# Main.net
KiCad netlist of a schematic drawn in Altium Designer
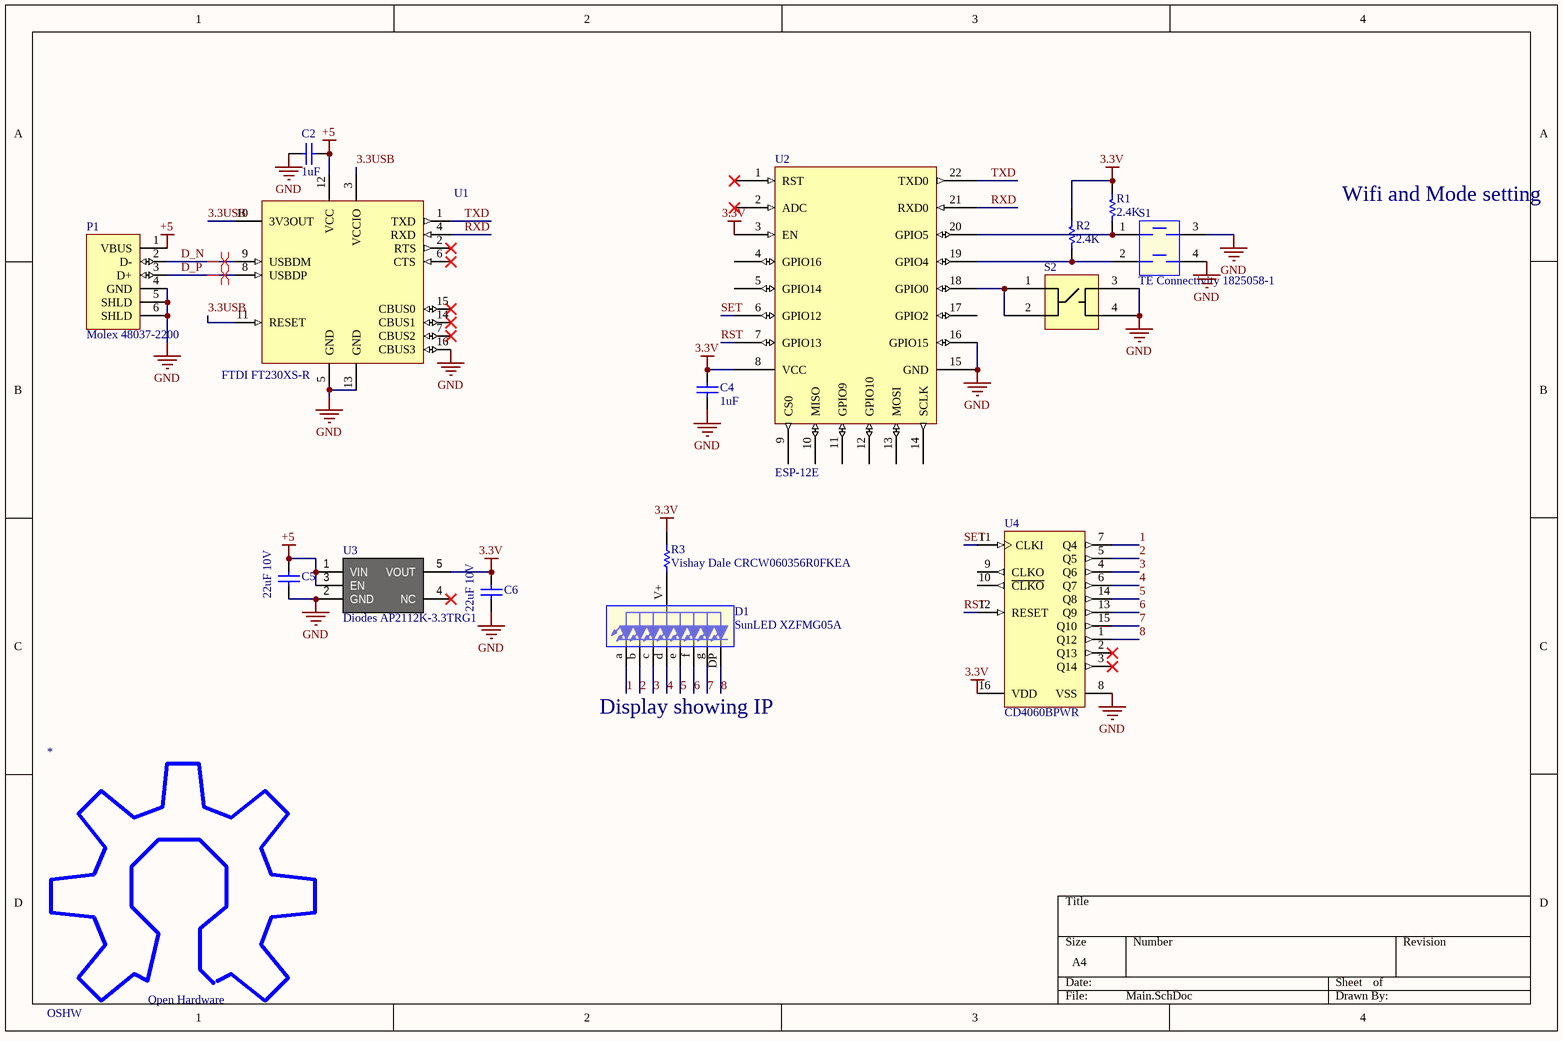
[diagram p0: Main.SchDoc]

(export (version "E")
  (design (tool "Eeschema 10.0.6"))
  (components
    (comp (ref "*")
      (value "OSHW")
      (footprint "PCB-wvhvgo6g2u4p9maf3omu-1")
      (libsource (lib "FavoritesLibrary") (part "SYM-yq9j37g916g0fiiuunoj-1"))
    )
    (comp (ref "C2")
      (value "1uF")
      (footprint "CAPC1608X90X35ML15T15")
      (description "CAP CER 1UF 16V 10% X5R 0603")
      (libsource (lib "CommunityVault") (part "CMP-126011-2"))
    )
    (comp (ref "C4")
      (value "1uF")
      (footprint "CAPC1608X90X35ML15T15")
      (description "CAP CER 1UF 16V 10% X5R 0603")
      (libsource (lib "CommunityVault") (part "CMP-126011-2"))
    )
    (comp (ref "C5")
      (value "22uF 10V")
      (footprint "CAPC3216X88X50NL20T25")
      (description "CAP CER 22UF 10V Y5V 1206")
      (fields
        (field (name "TOLERANCE") "-20%, +80%")
        (field (name "MANUFACTURER PART NUMBER") "LMK316F226ZL-T")
      )
      (libsource (lib "CommunityVault") (part "CMP-120806-1"))
    )
    (comp (ref "C6")
      (value "22uF 10V")
      (footprint "CAPC3216X88X50NL20T25")
      (description "CAP CER 22UF 10V Y5V 1206")
      (fields
        (field (name "TOLERANCE") "-20%, +80%")
        (field (name "MANUFACTURER PART NUMBER") "LMK316F226ZL-T")
      )
      (libsource (lib "CommunityVault") (part "CMP-120806-1"))
    )
    (comp (ref "D1")
      (value "SunLED XZFMG05A")
      (footprint "PCB-oie4hyh8z6kz1fe8odf0-1")
      (description "Display Led 0.2\" Green Ca Smd")
      (fields (field (name "MANUFACTURER PART NUMBER") "XZFMG05A"))
      (libsource (lib "CommunityVault") (part "SYM-790ab255a53aa6cd-1"))
    )
    (comp (ref "P1")
      (value "Molex 48037-2200")
      (footprint "PCB-2v2vzbs0gio7atqgwime-1")
      (description "Conn.; Data; USB; Plug; Shielded; Type A; Rt. Angle; SMT; Gold Plating")
      (fields (field (name "MANUFACTURER PART NUMBER") "48037-2200"))
      (libsource (lib "FavoritesLibrary") (part "SYM-d9a510daebca0662-1"))
    )
    (comp (ref "R1")
      (value "2.4K")
      (footprint "RESC1608X55X25ML10T15")
      (description "Res Thick Film 0603 2.4K Ohm 5% 1/10W 100ppm/C Molded SMD SMD Paper T/R")
      (fields
        (field (name "MANUFACTURER") "Philips (Mepco)")
        (field (name "MANUFACTURER PART NUMBER") "RC0603JR-072K4L")
      )
      (libsource (lib "CommunityVault") (part "CMP-13559605-1"))
    )
    (comp (ref "R2")
      (value "2.4K")
      (footprint "RESC1608X55X25ML10T15")
      (description "Res Thick Film 0603 2.4K Ohm 5% 1/10W 100ppm/C Molded SMD SMD Paper T/R")
      (fields
        (field (name "MANUFACTURER") "Philips (Mepco)")
        (field (name "MANUFACTURER PART NUMBER") "RC0603JR-072K4L")
      )
      (libsource (lib "CommunityVault") (part "CMP-13559605-1"))
    )
    (comp (ref "R3")
      (value "Vishay Dale CRCW060356R0FKEA")
      (footprint "RESC1609X50X30LL10T20")
      (description "RES SMD 56 OHM 1% 1/10W 0603")
      (libsource (lib "CommunityVault") (part "RES-2"))
    )
    (comp (ref "S1")
      (value "TE Connectivity 1825058-1")
      (footprint "PCB-oate9ly85fgayrvi93ce-1")
      (description "Switch DIP OFF ON SPST 2 Raised Slide 0.1A 24VDC Gull Wing 2.54mm SMD Tube")
      (fields (field (name "MANUFACTURER PART NUMBER") "1825058-1"))
      (libsource (lib "FavoritesLibrary") (part "SYM-446e8fa1c71e9ba9-1"))
    )
    (comp (ref "S2")
      (value "TE Connectivity (Tyco Electronics) / ALCOSWITCH FSM4JSMATR")
      (footprint "PCB-1274972-1")
      (description "SWITCH TACTILE SPST-NO 0.05A 24V")
      (libsource (lib "CommunityVault") (part "CMP-1274972-2"))
    )
    (comp (ref "U1")
      (value "FTDI FT230XS-R")
      (footprint "SSOP16-0.635-5X4MM")
      (description "Interface; USB-basic UART; Number of pins CBUS: 4; tape; SSOP16")
      (fields (field (name "MANUFACTURER PART NUMBER") "FT230XS-R"))
      (libsource (lib "CommunityVault") (part "FTDI-FT230XS-R-16"))
    )
    (comp (ref "U2")
      (value "ESP-12E")
      (footprint "PCB-20357682-7")
      (description "ESP8266 WiFi Module - ESP-12E")
      (libsource (lib "CommunityVault") (part "SYM-20357682-8"))
    )
    (comp (ref "U3")
      (value "Diodes AP2112K-3.3TRG1")
      (footprint "PCB-15095236-1")
      (description "IC REG LDO 3.3V 0.6A SOT25")
      (libsource (lib "CommunityVault") (part "SYM-15095236-1"))
    )
    (comp (ref "U4")
      (value "CD4060BPWR")
      (footprint "TI-PW16_N")
      (libsource (lib "CommunityVault") (part "TI-CD4060B-16"))
    )
  )
  (nets
    (net (code "1") (name "+5") (class "Default")
      (node (ref "C2") (pin "2") (pinfunction "2_2") (pintype "passive"))
      (node (ref "C5") (pin "2") (pinfunction "2_2") (pintype "passive"))
      (node (ref "P1") (pin "1") (pinfunction "VBUS_1") (pintype "power_in"))
      (node (ref "U1") (pin "12") (pinfunction "VCC_12") (pintype "power_in"))
      (node (ref "U3") (pin "1") (pinfunction "VIN_1") (pintype "passive"))
      (node (ref "U3") (pin "3") (pinfunction "EN_3") (pintype "passive"))
    )
    (net (code "2") (name "/1") (class "Default")
      (node (ref "D1") (pin "a") (pintype "passive"))
      (node (ref "U4") (pin "7") (pinfunction "Q4_7") (pintype "output"))
    )
    (net (code "3") (name "/2") (class "Default")
      (node (ref "D1") (pin "b") (pintype "passive"))
      (node (ref "U4") (pin "5") (pinfunction "Q5_5") (pintype "output"))
    )
    (net (code "4") (name "/3") (class "Default")
      (node (ref "D1") (pin "c") (pintype "passive"))
      (node (ref "U4") (pin "4") (pinfunction "Q6_4") (pintype "output"))
    )
    (net (code "5") (name "/3.3USB") (class "Default")
      (node (ref "U1") (pin "10") (pinfunction "3V3OUT_10") (pintype "power_in"))
      (node (ref "U1") (pin "11") (pinfunction "RESET_11") (pintype "input"))
      (node (ref "U1") (pin "3") (pinfunction "VCCIO_3") (pintype "power_in"))
    )
    (net (code "6") (name "/4") (class "Default")
      (node (ref "D1") (pin "d") (pintype "passive"))
      (node (ref "U4") (pin "6") (pinfunction "Q7_6") (pintype "output"))
    )
    (net (code "7") (name "/5") (class "Default")
      (node (ref "D1") (pin "e") (pintype "passive"))
      (node (ref "U4") (pin "14") (pinfunction "Q8_14") (pintype "output"))
    )
    (net (code "8") (name "/6") (class "Default")
      (node (ref "D1") (pin "f") (pintype "passive"))
      (node (ref "U4") (pin "13") (pinfunction "Q9_13") (pintype "output"))
    )
    (net (code "9") (name "/7") (class "Default")
      (node (ref "D1") (pin "g") (pintype "passive"))
      (node (ref "U4") (pin "15") (pinfunction "Q10_15") (pintype "output"))
    )
    (net (code "10") (name "/8") (class "Default")
      (node (ref "D1") (pin "DP") (pintype "passive"))
      (node (ref "U4") (pin "1") (pinfunction "Q12_1") (pintype "output"))
    )
    (net (code "11") (name "/D_N") (class "Default")
      (node (ref "P1") (pin "2") (pinfunction "D-_2") (pintype "bidirectional"))
      (node (ref "U1") (pin "9") (pinfunction "USBDM_9") (pintype "input"))
    )
    (net (code "12") (name "/D_P") (class "Default")
      (node (ref "P1") (pin "3") (pinfunction "D+_3") (pintype "bidirectional"))
      (node (ref "U1") (pin "8") (pinfunction "USBDP_8") (pintype "input"))
    )
    (net (code "13") (name "/RST") (class "Default")
      (node (ref "U2") (pin "7") (pinfunction "GPIO13_7") (pintype "bidirectional"))
      (node (ref "U4") (pin "12") (pinfunction "RESET_12") (pintype "input"))
    )
    (net (code "14") (name "/RXD") (class "Default")
      (node (ref "U1") (pin "4") (pinfunction "RXD_4") (pintype "input"))
      (node (ref "U2") (pin "21") (pinfunction "RXD0_21") (pintype "input"))
    )
    (net (code "15") (name "/SET") (class "Default")
      (node (ref "U2") (pin "6") (pinfunction "GPIO12_6") (pintype "bidirectional"))
      (node (ref "U4") (pin "11") (pinfunction "CLKI_11") (pintype "input"))
    )
    (net (code "16") (name "/TXD") (class "Default")
      (node (ref "U1") (pin "1") (pinfunction "TXD_1") (pintype "output"))
      (node (ref "U2") (pin "22") (pinfunction "TXD0_22") (pintype "output"))
    )
    (net (code "17") (name "3.3V") (class "Default")
      (node (ref "C4") (pin "2") (pinfunction "2_2") (pintype "passive"))
      (node (ref "C6") (pin "2") (pinfunction "2_2") (pintype "passive"))
      (node (ref "R1") (pin "2") (pinfunction "2_2") (pintype "passive"))
      (node (ref "R2") (pin "2") (pinfunction "2_2") (pintype "passive"))
      (node (ref "R3") (pin "2") (pinfunction "2_2") (pintype "passive"))
      (node (ref "U2") (pin "3") (pinfunction "EN_3") (pintype "input"))
      (node (ref "U2") (pin "8") (pinfunction "VCC_8") (pintype "power_in"))
      (node (ref "U3") (pin "5") (pinfunction "VOUT_5") (pintype "passive"))
      (node (ref "U4") (pin "16") (pinfunction "VDD_16") (pintype "power_in"))
    )
    (net (code "18") (name "GND") (class "Default")
      (node (ref "C2") (pin "1") (pinfunction "1_1") (pintype "passive"))
      (node (ref "C4") (pin "1") (pinfunction "1_1") (pintype "passive"))
      (node (ref "C5") (pin "1") (pinfunction "1_1") (pintype "passive"))
      (node (ref "C6") (pin "1") (pinfunction "1_1") (pintype "passive"))
      (node (ref "P1") (pin "4") (pinfunction "GND_4") (pintype "power_in"))
      (node (ref "P1") (pin "5") (pinfunction "SHLD_5") (pintype "passive"))
      (node (ref "P1") (pin "6") (pinfunction "SHLD_6") (pintype "passive"))
      (node (ref "S1") (pin "3") (pinfunction "3_3") (pintype "passive"))
      (node (ref "S1") (pin "4") (pinfunction "4_4") (pintype "passive"))
      (node (ref "S2") (pin "3") (pinfunction "3_3") (pintype "passive"))
      (node (ref "S2") (pin "4") (pinfunction "4_4") (pintype "passive"))
      (node (ref "U1") (pin "13") (pinfunction "GND_13") (pintype "power_in"))
      (node (ref "U1") (pin "16") (pinfunction "CBUS3_16") (pintype "bidirectional"))
      (node (ref "U1") (pin "5") (pinfunction "GND_5") (pintype "power_in"))
      (node (ref "U2") (pin "15") (pinfunction "GND_15") (pintype "power_in"))
      (node (ref "U2") (pin "16") (pinfunction "GPIO15_16") (pintype "bidirectional"))
      (node (ref "U3") (pin "2") (pinfunction "GND_2") (pintype "passive"))
      (node (ref "U4") (pin "8") (pinfunction "VSS_8") (pintype "power_in"))
    )
    (net (code "19") (name "Net-(D1-PadV+)") (class "Default")
      (node (ref "D1") (pin "V+") (pinfunction "V+_V+") (pintype "passive"))
      (node (ref "R3") (pin "1") (pinfunction "1_1") (pintype "passive"))
    )
    (net (code "20") (name "Net-(U2-GPIO0)") (class "Default")
      (node (ref "S2") (pin "1") (pinfunction "1_1") (pintype "passive"))
      (node (ref "S2") (pin "2") (pinfunction "2_2") (pintype "passive"))
      (node (ref "U2") (pin "18") (pinfunction "GPIO0_18") (pintype "bidirectional"))
    )
    (net (code "21") (name "Net-(U2-GPIO4)") (class "Default")
      (node (ref "R2") (pin "1") (pinfunction "1_1") (pintype "passive"))
      (node (ref "S1") (pin "2") (pinfunction "2_2") (pintype "passive"))
      (node (ref "U2") (pin "19") (pinfunction "GPIO4_19") (pintype "bidirectional"))
    )
    (net (code "22") (name "Net-(U2-GPIO5)") (class "Default")
      (node (ref "R1") (pin "1") (pinfunction "1_1") (pintype "passive"))
      (node (ref "S1") (pin "1") (pinfunction "1_1") (pintype "passive"))
      (node (ref "U2") (pin "20") (pinfunction "GPIO5_20") (pintype "bidirectional"))
    )
    (net (code "23") (name "unconnected-(U1-CBUS0-Pad15)") (class "Default")
      (node (ref "U1") (pin "15") (pinfunction "CBUS0_15") (pintype "bidirectional+no_connect"))
    )
    (net (code "24") (name "unconnected-(U1-CBUS1-Pad14)") (class "Default")
      (node (ref "U1") (pin "14") (pinfunction "CBUS1_14") (pintype "bidirectional+no_connect"))
    )
    (net (code "25") (name "unconnected-(U1-CBUS2-Pad7)") (class "Default")
      (node (ref "U1") (pin "7") (pinfunction "CBUS2_7") (pintype "bidirectional+no_connect"))
    )
    (net (code "26") (name "unconnected-(U1-CTS-Pad6)") (class "Default")
      (node (ref "U1") (pin "6") (pinfunction "CTS_6") (pintype "input+no_connect"))
    )
    (net (code "27") (name "unconnected-(U1-RTS-Pad2)") (class "Default")
      (node (ref "U1") (pin "2") (pinfunction "RTS_2") (pintype "output+no_connect"))
    )
    (net (code "28") (name "unconnected-(U2-ADC-Pad2)") (class "Default")
      (node (ref "U2") (pin "2") (pinfunction "ADC_2") (pintype "input+no_connect"))
    )
    (net (code "29") (name "unconnected-(U2-CS0-Pad9)") (class "Default")
      (node (ref "U2") (pin "9") (pinfunction "CS0_9") (pintype "output"))
    )
    (net (code "30") (name "unconnected-(U2-GPIO2-Pad17)") (class "Default")
      (node (ref "U2") (pin "17") (pinfunction "GPIO2_17") (pintype "bidirectional"))
    )
    (net (code "31") (name "unconnected-(U2-GPIO9-Pad11)") (class "Default")
      (node (ref "U2") (pin "11") (pinfunction "GPIO9_11") (pintype "bidirectional"))
    )
    (net (code "32") (name "unconnected-(U2-GPIO10-Pad12)") (class "Default")
      (node (ref "U2") (pin "12") (pinfunction "GPIO10_12") (pintype "bidirectional"))
    )
    (net (code "33") (name "unconnected-(U2-GPIO14-Pad5)") (class "Default")
      (node (ref "U2") (pin "5") (pinfunction "GPIO14_5") (pintype "bidirectional"))
    )
    (net (code "34") (name "unconnected-(U2-GPIO16-Pad4)") (class "Default")
      (node (ref "U2") (pin "4") (pinfunction "GPIO16_4") (pintype "bidirectional"))
    )
    (net (code "35") (name "unconnected-(U2-MISO-Pad10)") (class "Default")
      (node (ref "U2") (pin "10") (pinfunction "MISO_10") (pintype "bidirectional"))
    )
    (net (code "36") (name "unconnected-(U2-MOSI-Pad13)") (class "Default")
      (node (ref "U2") (pin "13") (pinfunction "MOSI_13") (pintype "bidirectional"))
    )
    (net (code "37") (name "unconnected-(U2-RST-Pad1)") (class "Default")
      (node (ref "U2") (pin "1") (pinfunction "RST_1") (pintype "input+no_connect"))
    )
    (net (code "38") (name "unconnected-(U2-SCLK-Pad14)") (class "Default")
      (node (ref "U2") (pin "14") (pinfunction "SCLK_14") (pintype "output"))
    )
    (net (code "39") (name "unconnected-(U3-NC-Pad4)") (class "Default")
      (node (ref "U3") (pin "4") (pinfunction "NC_4") (pintype "passive+no_connect"))
    )
    (net (code "40") (name "unconnected-(U4-CLKO-Pad9)") (class "Default")
      (node (ref "U4") (pin "9") (pinfunction "CLKO_9") (pintype "output"))
    )
    (net (code "41") (name "unconnected-(U4-Q13-Pad2)") (class "Default")
      (node (ref "U4") (pin "2") (pinfunction "Q13_2") (pintype "output+no_connect"))
    )
    (net (code "42") (name "unconnected-(U4-Q14-Pad3)") (class "Default")
      (node (ref "U4") (pin "3") (pinfunction "Q14_3") (pintype "output+no_connect"))
    )
    (net (code "43") (name "unconnected-(U4-~{CLKO}-Pad10)") (class "Default")
      (node (ref "U4") (pin "10") (pinfunction "~{CLKO}_10") (pintype "output"))
    )
  )
)
